# OSC.net
KiCad netlist of a schematic drawn in Altium Designer
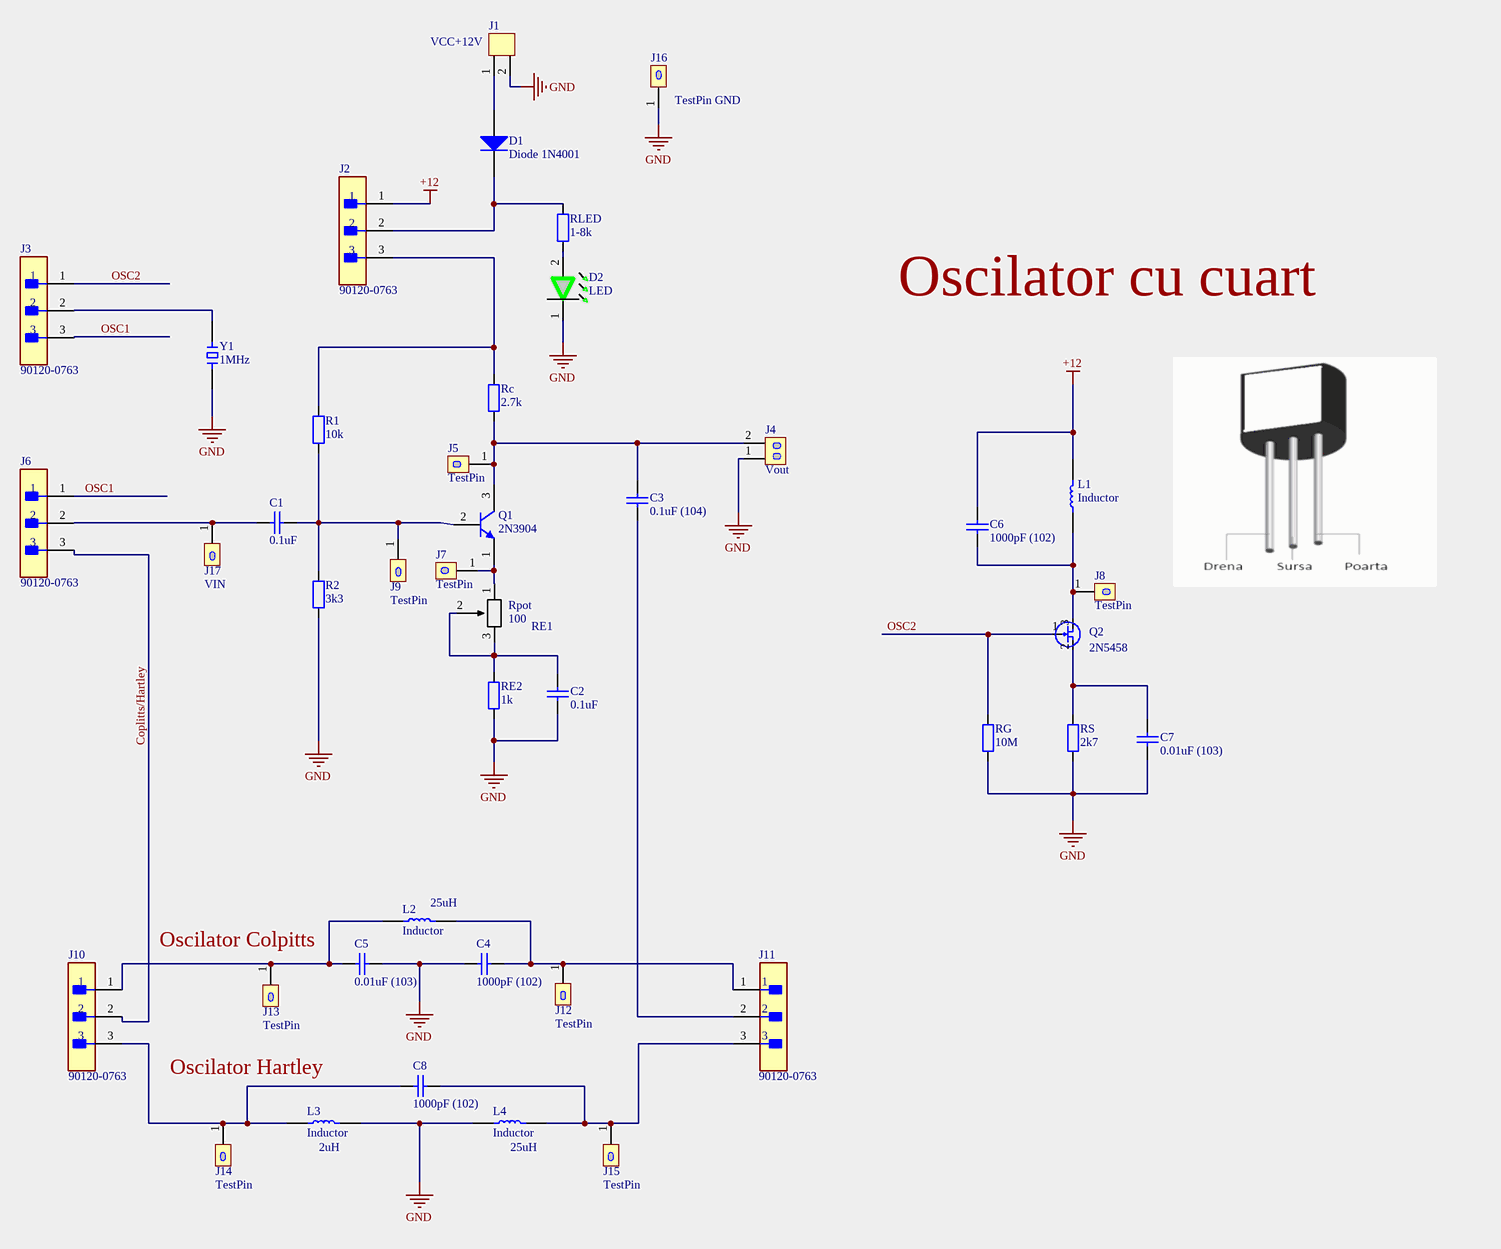
[diagram p0: OSC.SchDoc]

(export (version "E")
  (design (tool "Eeschema 10.0.6"))
  (components
    (comp (ref "C1")
      (value "0.1uF")
      (footprint "CAP4.5mm")
      (description "104 cap")
      (libsource (lib "OSC") (part "CAP 104"))
    )
    (comp (ref "C2")
      (value "0.1uF")
      (footprint "CAP4.5mm")
      (description "104 cap")
      (libsource (lib "OSC") (part "CAP 104"))
    )
    (comp (ref "C3")
      (value "0.1uF (104)")
      (footprint "CAP4.5mm")
      (description "104 cap")
      (libsource (lib "OSC") (part "CAP 104"))
    )
    (comp (ref "C4")
      (value "1000pF (102)")
      (footprint "CAP4.5mm")
      (description "104 cap")
      (libsource (lib "OSC") (part "CAP 104"))
    )
    (comp (ref "C5")
      (value "0.01uF (103)")
      (footprint "CAP4.5mm")
      (description "104 cap")
      (libsource (lib "OSC") (part "CAP 104"))
    )
    (comp (ref "C6")
      (value "1000pF (102)")
      (footprint "CAP4.5mm")
      (description "104 cap")
      (libsource (lib "OSC") (part "CAP 104"))
    )
    (comp (ref "C7")
      (value "0.01uF (103)")
      (footprint "CAP4.5mm")
      (description "104 cap")
      (libsource (lib "OSC") (part "CAP 104"))
    )
    (comp (ref "C8")
      (value "1000pF (102)")
      (footprint "CAP4.5mm")
      (description "104 cap")
      (libsource (lib "OSC") (part "CAP 104"))
    )
    (comp (ref "D1")
      (value "Diode 1N4001")
      (footprint "DO-41")
      (description "1 Amp General Purpose Rectifier")
      (fields (field (name "PUBLISHER") "Altium Limited"))
      (libsource (lib "Miscellaneous Devices") (part "Diode 1N4001"))
    )
    (comp (ref "D2") (value "LED") (footprint "LED") (libsource (lib "CEF") (part "LED")))
    (comp (ref "J1")
      (value "VCC+12V")
      (footprint "HDR_1X2_TE")
      (description "Connector, 2-Ports")
      (libsource (lib "CEF") (part "CON_1x2"))
    )
    (comp (ref "J2")
      (value "90120-0763")
      (footprint "FP-90120-0763-MFG")
      (description "CONN HEADER VERT 3POS 2.54MM")
      (fields
        (field (name "MANUFACTURER") "Molex")
        (field (name "OCTOPART") "https://octopart.com/90120-0763-molex-655433")
      )
      (libsource (lib "Altium Content Vault") (part "0d3f023dd272f625e17a2be33dea85f"))
    )
    (comp (ref "J3")
      (value "90120-0763")
      (footprint "FP-90120-0763-MFG")
      (description "CONN HEADER VERT 3POS 2.54MM")
      (fields
        (field (name "MANUFACTURER") "Molex")
        (field (name "OCTOPART") "https://octopart.com/90120-0763-molex-655433")
      )
      (libsource (lib "Altium Content Vault") (part "0d3f023dd272f625e17a2be33dea85f"))
    )
    (comp (ref "J4")
      (value "Vout")
      (footprint "HDR_1x2_pin")
      (description "Header, 2-Pin")
      (libsource (lib "CEF") (part "HDR_1x2"))
    )
    (comp (ref "J5") (value "TestPin") (footprint "HDR_1x1_pin") (libsource (lib "") (part "Test Pin_3")))
    (comp (ref "J6")
      (value "90120-0763")
      (footprint "FP-90120-0763-MFG")
      (description "CONN HEADER VERT 3POS 2.54MM")
      (fields
        (field (name "MANUFACTURER") "Molex")
        (field (name "OCTOPART") "https://octopart.com/90120-0763-molex-655433")
      )
      (libsource (lib "Altium Content Vault") (part "0d3f023dd272f625e17a2be33dea85f"))
    )
    (comp (ref "J7") (value "TestPin") (footprint "HDR_1x1_pin") (libsource (lib "") (part "Test Pin_3")))
    (comp (ref "J8") (value "TestPin") (footprint "HDR_1x1_pin") (libsource (lib "") (part "Test Pin_2")))
    (comp (ref "J9") (value "TestPin") (footprint "HDR_1x1_pin") (libsource (lib "CEF") (part "Test Pin")))
    (comp (ref "J10")
      (value "90120-0763")
      (footprint "FP-90120-0763-MFG")
      (description "CONN HEADER VERT 3POS 2.54MM")
      (fields
        (field (name "MANUFACTURER") "Molex")
        (field (name "OCTOPART") "https://octopart.com/90120-0763-molex-655433")
      )
      (libsource (lib "Altium Content Vault") (part "0d3f023dd272f625e17a2be33dea85f"))
    )
    (comp (ref "J11")
      (value "90120-0763")
      (footprint "FP-90120-0763-MFG")
      (description "CONN HEADER VERT 3POS 2.54MM")
      (fields
        (field (name "MANUFACTURER") "Molex")
        (field (name "OCTOPART") "https://octopart.com/90120-0763-molex-655433")
      )
      (libsource (lib "") (part "0d3f023dd272f625e17a2be33dea85f_1"))
    )
    (comp (ref "J12") (value "TestPin") (footprint "HDR_1x1_pin") (libsource (lib "CEF") (part "Test Pin")))
    (comp (ref "J13") (value "TestPin") (footprint "HDR_1x1_pin") (libsource (lib "CEF") (part "Test Pin")))
    (comp (ref "J14") (value "TestPin") (footprint "HDR_1x1_pin") (libsource (lib "CEF") (part "Test Pin")))
    (comp (ref "J15") (value "TestPin") (footprint "HDR_1x1_pin") (libsource (lib "CEF") (part "Test Pin")))
    (comp (ref "J16")
      (value "TestPin GND")
      (footprint "HDR_1x1_pin")
      (libsource (lib "") (part "Test Pin_1"))
    )
    (comp (ref "J17") (value "VIN") (footprint "HDR_1x1_pin") (libsource (lib "CEF") (part "Test Pin")))
    (comp (ref "L1") (value "Inductor") (footprint "Inductor1") (libsource (lib "CEF") (part "Inductor")))
    (comp (ref "L2") (value "Inductor") (footprint "Inductor1") (libsource (lib "CEF") (part "Inductor")))
    (comp (ref "L3") (value "Inductor") (footprint "Inductor1") (libsource (lib "CEF") (part "Inductor")))
    (comp (ref "L4") (value "Inductor") (footprint "Inductor1") (libsource (lib "CEF") (part "Inductor")))
    (comp (ref "Q1")
      (value "2N3904")
      (footprint "ONSC-TO-92-3-29-11")
      (description "General Purpose Transistor, NPN Silicon, 200 mA, 60 V, -55 to 150 degC, 3-Pin TO-92, RoHS, Bulk")
      (fields (field (name "MANUFACTURER") "ONSemiconductor"))
      (libsource (lib "Altium Content Vault") (part "BJT-NPN-EBC-3"))
    )
    (comp (ref "Q2") (value "2N5458") (footprint "2N5458") (libsource (lib "CEF") (part "JFET N 2N5458")))
    (comp (ref "R1")
      (value "10k")
      (footprint "Resistor")
      (description "0.25W,Axial")
      (libsource (lib "CEF") (part "Resistor 0.25W 5mm"))
    )
    (comp (ref "R2")
      (value "3k3")
      (footprint "Resistor")
      (description "0.25W,Axial")
      (libsource (lib "CEF") (part "Resistor 0.25W 5mm"))
    )
    (comp (ref "Rc")
      (value "2.7k")
      (footprint "Resistor")
      (description "0.25W,Axial")
      (libsource (lib "CEF") (part "Resistor 0.25W 5mm"))
    )
    (comp (ref "RE1") (value "Rpot100ohm") (footprint "Potentiometer") (libsource (lib "CEF") (part "Rpot")))
    (comp (ref "RE2")
      (value "1k")
      (footprint "Resistor")
      (description "0.25W,Axial")
      (libsource (lib "CEF") (part "Resistor 0.25W 5mm"))
    )
    (comp (ref "RG")
      (value "10M")
      (footprint "Resistor")
      (description "0.25W,Axial")
      (libsource (lib "CEF") (part "Resistor 0.25W 5mm"))
    )
    (comp (ref "RLED")
      (value "1-8k")
      (footprint "Resistor")
      (description "0.25W,Axial")
      (libsource (lib "CEF") (part "Resistor 0.25W 5mm"))
    )
    (comp (ref "RS")
      (value "2k7")
      (footprint "Resistor")
      (description "0.25W,Axial")
      (libsource (lib "CEF") (part "Resistor 0.25W 5mm"))
    )
    (comp (ref "Y1") (value "1MHz") (footprint "XTAL") (libsource (lib "CEF") (part "Xtal")))
  )
  (nets
    (net (code "1") (name "+12") (class "Default")
      (node (ref "C6") (pin "2") (pinfunction "2_2") (pintype "passive"))
      (node (ref "J2") (pin "1") (pinfunction "1_1") (pintype "passive"))
      (node (ref "L1") (pin "1") (pinfunction "1_1") (pintype "passive"))
    )
    (net (code "2") (name "/Coplitts{slash}Hartley") (class "Default")
      (node (ref "J10") (pin "2") (pinfunction "2_2") (pintype "passive"))
      (node (ref "J6") (pin "3") (pinfunction "3_3") (pintype "passive"))
    )
    (net (code "3") (name "/OSC1") (class "Default")
      (node (ref "J3") (pin "3") (pinfunction "3_3") (pintype "passive"))
      (node (ref "J6") (pin "1") (pinfunction "1_1") (pintype "passive"))
    )
    (net (code "4") (name "/OSC2") (class "Default")
      (node (ref "J3") (pin "1") (pinfunction "1_1") (pintype "passive"))
      (node (ref "Q2") (pin "1") (pinfunction "1_1") (pintype "passive"))
      (node (ref "RG") (pin "2") (pinfunction "2_2") (pintype "passive"))
    )
    (net (code "5") (name "GND") (class "Default")
      (node (ref "C2") (pin "2") (pinfunction "2_2") (pintype "passive"))
      (node (ref "C4") (pin "1") (pinfunction "1_1") (pintype "passive"))
      (node (ref "C5") (pin "2") (pinfunction "2_2") (pintype "passive"))
      (node (ref "C7") (pin "1") (pinfunction "1_1") (pintype "passive"))
      (node (ref "D2") (pin "1") (pinfunction "1_1") (pintype "passive"))
      (node (ref "J1") (pin "2") (pinfunction "2_2") (pintype "passive"))
      (node (ref "J16") (pin "1") (pinfunction "1_1") (pintype "passive"))
      (node (ref "J4") (pin "1") (pinfunction "1_1") (pintype "passive"))
      (node (ref "L3") (pin "1") (pinfunction "1_1") (pintype "passive"))
      (node (ref "L4") (pin "2") (pinfunction "2_2") (pintype "passive"))
      (node (ref "R2") (pin "1") (pinfunction "1_1") (pintype "passive"))
      (node (ref "RE2") (pin "1") (pinfunction "1_1") (pintype "passive"))
      (node (ref "RG") (pin "1") (pinfunction "1_1") (pintype "passive"))
      (node (ref "RS") (pin "1") (pinfunction "1_1") (pintype "passive"))
      (node (ref "Y1") (pin "1") (pinfunction "1_1") (pintype "passive"))
    )
    (net (code "6") (name "Net-(C1-Pad1)") (class "Default")
      (node (ref "C1") (pin "1") (pinfunction "1_1") (pintype "passive"))
      (node (ref "J17") (pin "1") (pinfunction "1_1") (pintype "passive"))
      (node (ref "J6") (pin "2") (pinfunction "2_2") (pintype "passive"))
    )
    (net (code "7") (name "Net-(C2-Pad1)") (class "Default")
      (node (ref "C2") (pin "1") (pinfunction "1_1") (pintype "passive"))
      (node (ref "RE1") (pin "2") (pintype "passive"))
      (node (ref "RE1") (pin "3") (pintype "passive"))
      (node (ref "RE2") (pin "2") (pinfunction "2_2") (pintype "passive"))
    )
    (net (code "8") (name "Net-(C3-Pad2)") (class "Default")
      (node (ref "C3") (pin "2") (pinfunction "2_2") (pintype "passive"))
      (node (ref "J11") (pin "2") (pinfunction "2_2") (pintype "passive"))
    )
    (net (code "9") (name "Net-(C4-Pad2)") (class "Default")
      (node (ref "C4") (pin "2") (pinfunction "2_2") (pintype "passive"))
      (node (ref "J11") (pin "1") (pinfunction "1_1") (pintype "passive"))
      (node (ref "J12") (pin "1") (pinfunction "1_1") (pintype "passive"))
      (node (ref "L2") (pin "1") (pinfunction "1_1") (pintype "passive"))
    )
    (net (code "10") (name "Net-(C5-Pad1)") (class "Default")
      (node (ref "C5") (pin "1") (pinfunction "1_1") (pintype "passive"))
      (node (ref "J10") (pin "1") (pinfunction "1_1") (pintype "passive"))
      (node (ref "J13") (pin "1") (pinfunction "1_1") (pintype "passive"))
      (node (ref "L2") (pin "2") (pinfunction "2_2") (pintype "passive"))
    )
    (net (code "11") (name "Net-(C8-Pad1)") (class "Default")
      (node (ref "C8") (pin "1") (pinfunction "1_1") (pintype "passive"))
      (node (ref "J10") (pin "3") (pinfunction "3_3") (pintype "passive"))
      (node (ref "J14") (pin "1") (pinfunction "1_1") (pintype "passive"))
      (node (ref "L3") (pin "2") (pinfunction "2_2") (pintype "passive"))
    )
    (net (code "12") (name "Net-(C8-Pad2)") (class "Default")
      (node (ref "C8") (pin "2") (pinfunction "2_2") (pintype "passive"))
      (node (ref "J11") (pin "3") (pinfunction "3_3") (pintype "passive"))
      (node (ref "J15") (pin "1") (pinfunction "1_1") (pintype "passive"))
      (node (ref "L4") (pin "1") (pinfunction "1_1") (pintype "passive"))
    )
    (net (code "13") (name "Net-(D1-A)") (class "Default")
      (node (ref "D1") (pin "1") (pinfunction "A_1") (pintype "passive"))
      (node (ref "J1") (pin "1") (pinfunction "1_1") (pintype "passive"))
    )
    (net (code "14") (name "Net-(D1-K)") (class "Default")
      (node (ref "D1") (pin "2") (pinfunction "K_2") (pintype "passive"))
      (node (ref "J2") (pin "2") (pinfunction "2_2") (pintype "passive"))
      (node (ref "RLED") (pin "2") (pinfunction "2_2") (pintype "passive"))
    )
    (net (code "15") (name "Net-(D2-Pad2)") (class "Default")
      (node (ref "D2") (pin "2") (pinfunction "2_2") (pintype "passive"))
      (node (ref "RLED") (pin "1") (pinfunction "1_1") (pintype "passive"))
    )
    (net (code "16") (name "Net-(J2-Pad3)") (class "Default")
      (node (ref "J2") (pin "3") (pinfunction "3_3") (pintype "passive"))
      (node (ref "R1") (pin "2") (pinfunction "2_2") (pintype "passive"))
      (node (ref "Rc") (pin "2") (pinfunction "2_2") (pintype "passive"))
    )
    (net (code "17") (name "Net-(J3-Pad2)") (class "Default")
      (node (ref "J3") (pin "2") (pinfunction "2_2") (pintype "passive"))
      (node (ref "Y1") (pin "2") (pinfunction "2_2") (pintype "passive"))
    )
    (net (code "18") (name "Net-(Q1-B)") (class "Default")
      (node (ref "C1") (pin "2") (pinfunction "2_2") (pintype "passive"))
      (node (ref "J9") (pin "1") (pinfunction "1_1") (pintype "passive"))
      (node (ref "Q1") (pin "2") (pinfunction "B_2") (pintype "passive"))
      (node (ref "R1") (pin "1") (pinfunction "1_1") (pintype "passive"))
      (node (ref "R2") (pin "2") (pinfunction "2_2") (pintype "passive"))
    )
    (net (code "19") (name "Net-(Q1-C)") (class "Default")
      (node (ref "C3") (pin "1") (pinfunction "1_1") (pintype "passive"))
      (node (ref "J4") (pin "2") (pinfunction "2_2") (pintype "passive"))
      (node (ref "J5") (pin "1") (pinfunction "1_1") (pintype "passive"))
      (node (ref "Q1") (pin "3") (pinfunction "C_3") (pintype "passive"))
      (node (ref "Rc") (pin "1") (pinfunction "1_1") (pintype "passive"))
    )
    (net (code "20") (name "Net-(Q1-E)") (class "Default")
      (node (ref "J7") (pin "1") (pinfunction "1_1") (pintype "passive"))
      (node (ref "Q1") (pin "1") (pinfunction "E_1") (pintype "passive"))
      (node (ref "RE1") (pin "1") (pintype "passive"))
    )
    (net (code "21") (name "Net-(Q2-D)") (class "Default")
      (node (ref "C6") (pin "1") (pinfunction "1_1") (pintype "passive"))
      (node (ref "J8") (pin "1") (pinfunction "1_1") (pintype "passive"))
      (node (ref "L1") (pin "2") (pinfunction "2_2") (pintype "passive"))
      (node (ref "Q2") (pin "3") (pinfunction "D_3") (pintype "passive"))
    )
    (net (code "22") (name "Net-(Q2-S)") (class "Default")
      (node (ref "C7") (pin "2") (pinfunction "2_2") (pintype "passive"))
      (node (ref "Q2") (pin "2") (pinfunction "S_2") (pintype "passive"))
      (node (ref "RS") (pin "2") (pinfunction "2_2") (pintype "passive"))
    )
  )
)
